# MD_02_SCHM.net
KiCad netlist of a schematic drawn in EAGLE
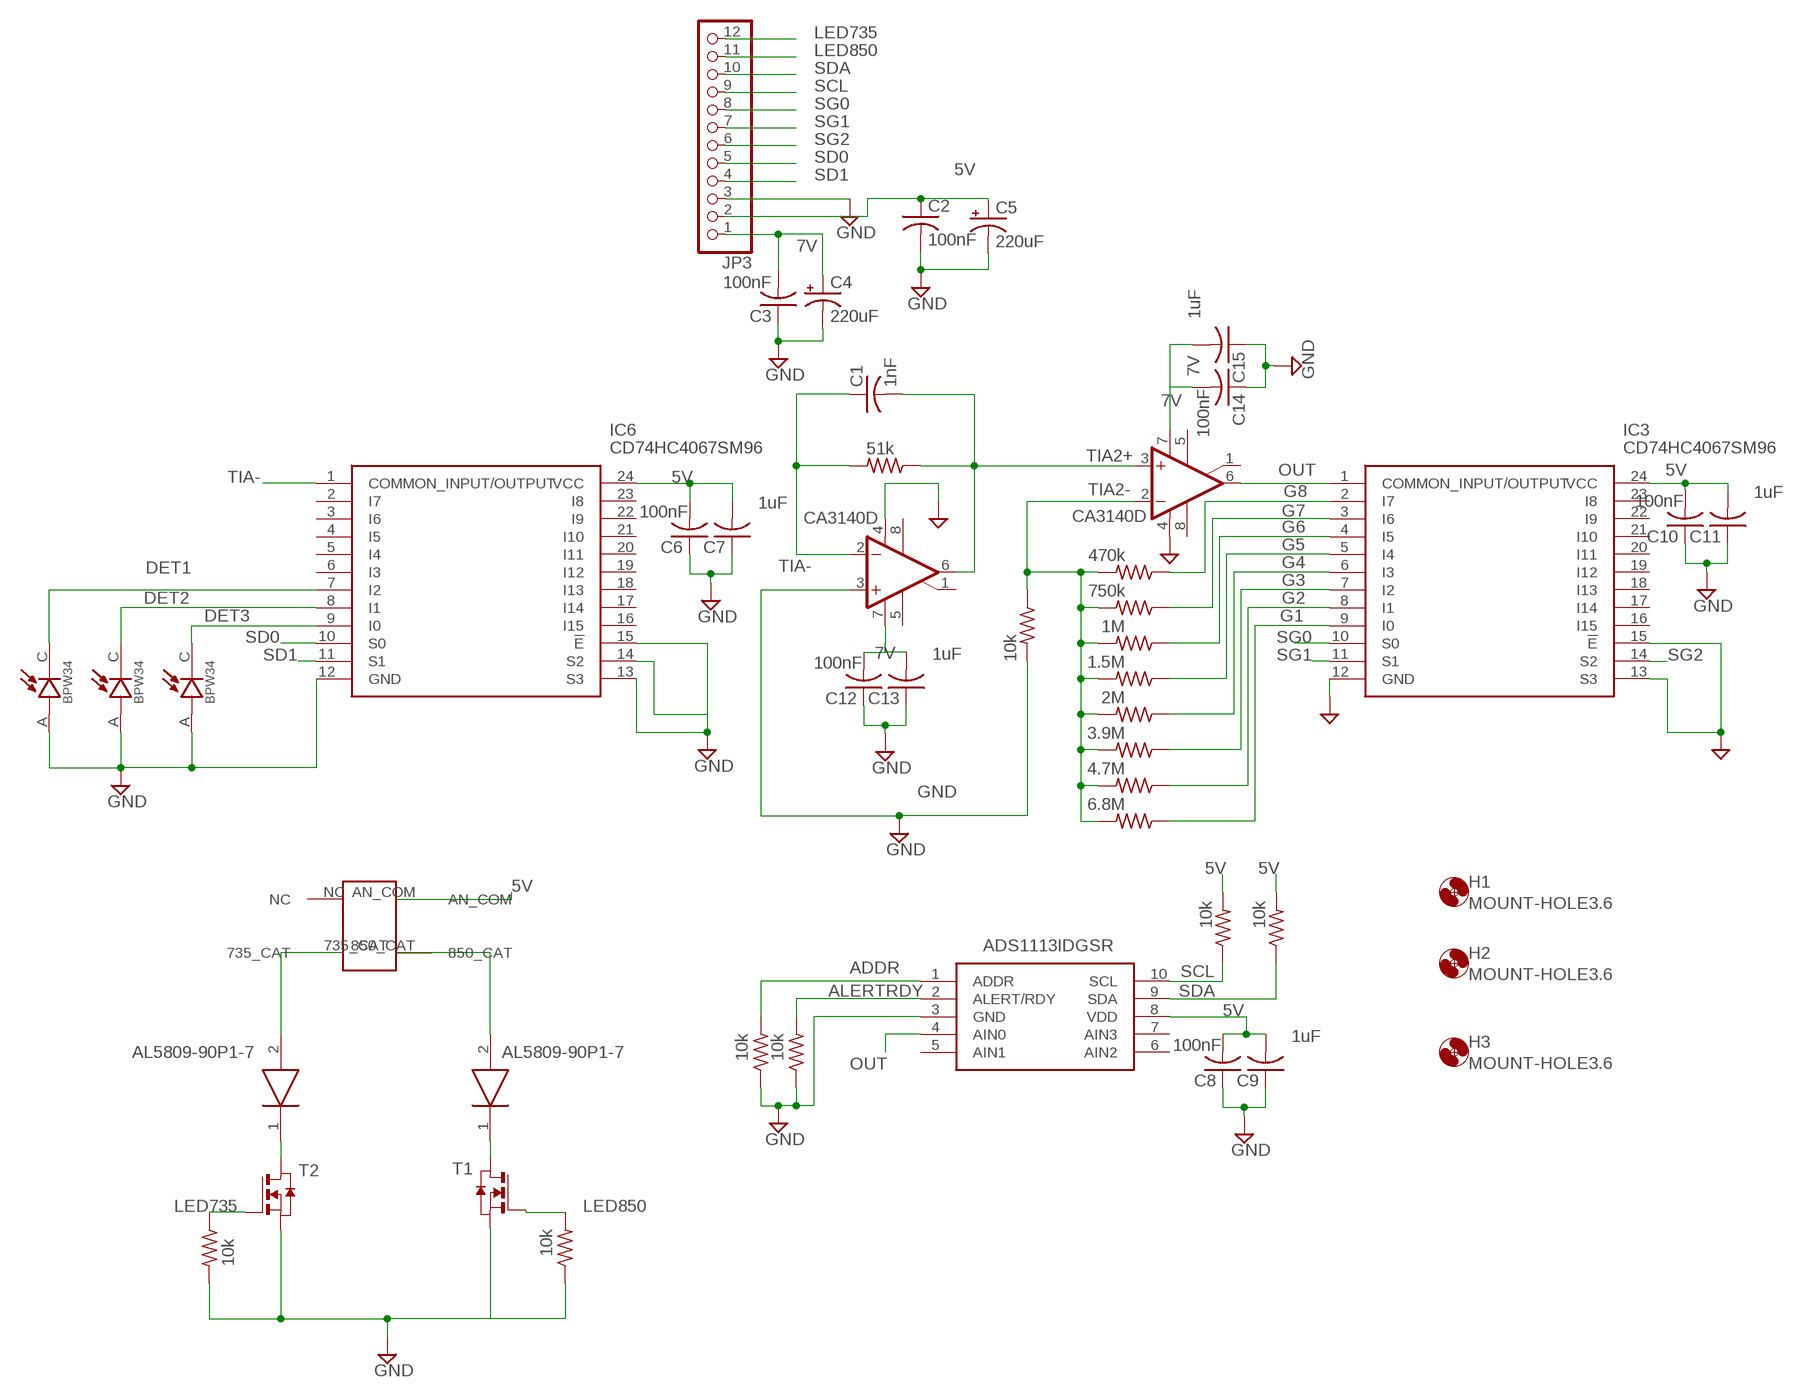
[diagram p0: schematic, sheet 1]

(export (version "E")
  (design (tool "Eeschema 10.0.6"))
  (components
    (comp (ref "C1")
      (value "1nF")
      (footprint "eagle-import:C0805")
      (libsource (lib "eagle-import") (part "C-USC0805"))
    )
    (comp (ref "C2")
      (value "100nF")
      (footprint "eagle-import:C0805")
      (libsource (lib "eagle-import") (part "C-USC0805"))
    )
    (comp (ref "C3")
      (value "100nF")
      (footprint "eagle-import:C0805")
      (libsource (lib "eagle-import") (part "C-USC0805"))
    )
    (comp (ref "C4")
      (value "220uF")
      (footprint "eagle-import:E5-6")
      (libsource (lib "eagle-import") (part "CPOL-USE5-6"))
    )
    (comp (ref "C5")
      (value "220uF")
      (footprint "eagle-import:E5-6")
      (libsource (lib "eagle-import") (part "CPOL-USE5-6"))
    )
    (comp (ref "C6")
      (value "100nF")
      (footprint "eagle-import:C0805")
      (libsource (lib "eagle-import") (part "C-USC0805"))
    )
    (comp (ref "C7")
      (value "1uF")
      (footprint "eagle-import:C0805")
      (libsource (lib "eagle-import") (part "C-USC0805"))
    )
    (comp (ref "C8")
      (value "100nF")
      (footprint "eagle-import:C0805")
      (libsource (lib "eagle-import") (part "C-USC0805"))
    )
    (comp (ref "C9")
      (value "1uF")
      (footprint "eagle-import:C0805")
      (libsource (lib "eagle-import") (part "C-USC0805"))
    )
    (comp (ref "C10")
      (value "100nF")
      (footprint "eagle-import:C0805")
      (libsource (lib "eagle-import") (part "C-USC0805"))
    )
    (comp (ref "C11")
      (value "1uF")
      (footprint "eagle-import:C0805")
      (libsource (lib "eagle-import") (part "C-USC0805"))
    )
    (comp (ref "C12")
      (value "100nF")
      (footprint "eagle-import:C0805")
      (libsource (lib "eagle-import") (part "C-USC0805"))
    )
    (comp (ref "C13")
      (value "1uF")
      (footprint "eagle-import:C0805")
      (libsource (lib "eagle-import") (part "C-USC0805"))
    )
    (comp (ref "C14")
      (value "100nF")
      (footprint "eagle-import:C0805")
      (libsource (lib "eagle-import") (part "C-USC0805"))
    )
    (comp (ref "C15")
      (value "1uF")
      (footprint "eagle-import:C0805")
      (libsource (lib "eagle-import") (part "C-USC0805"))
    )
    (comp (ref "D1")
      (value "AL5809-90P1-7")
      (footprint "eagle-import:SODFL3718X100N")
      (fields (field (name "MOUSER_PART_NUMBER") "621-AL5809-90P1-7"))
      (libsource (lib "eagle-import") (part "AL5809-90P1-7"))
    )
    (comp (ref "D2")
      (value "BPW34")
      (footprint "eagle-import:DIO_BPW34")
      (fields (field (name "MF") "Vishay Semiconductor"))
      (libsource (lib "eagle-import") (part "BPW34"))
    )
    (comp (ref "D3")
      (value "BPW34")
      (footprint "eagle-import:DIO_BPW34")
      (fields (field (name "MF") "Vishay Semiconductor"))
      (libsource (lib "eagle-import") (part "BPW34"))
    )
    (comp (ref "D4")
      (value "BPW34")
      (footprint "eagle-import:DIO_BPW34")
      (fields (field (name "MF") "Vishay Semiconductor"))
      (libsource (lib "eagle-import") (part "BPW34"))
    )
    (comp (ref "D5")
      (value "AL5809-90P1-7")
      (footprint "eagle-import:SODFL3718X100N")
      (fields (field (name "MOUSER_PART_NUMBER") "621-AL5809-90P1-7"))
      (libsource (lib "eagle-import") (part "AL5809-90P1-7"))
    )
    (comp (ref "H1")
      (value "MOUNT-HOLE3.6")
      (footprint "eagle-import:3,6")
      (libsource (lib "eagle-import") (part "MOUNT-HOLE3.6"))
    )
    (comp (ref "H2")
      (value "MOUNT-HOLE3.6")
      (footprint "eagle-import:3,6")
      (libsource (lib "eagle-import") (part "MOUNT-HOLE3.6"))
    )
    (comp (ref "H3")
      (value "MOUNT-HOLE3.6")
      (footprint "eagle-import:3,6")
      (libsource (lib "eagle-import") (part "MOUNT-HOLE3.6"))
    )
    (comp (ref "IC1")
      (value "CA3140D")
      (footprint "eagle-import:SO08")
      (libsource (lib "eagle-import") (part "CA3140D"))
    )
    (comp (ref "IC2")
      (value "CA3140D")
      (footprint "eagle-import:SO08")
      (libsource (lib "eagle-import") (part "CA3140D"))
    )
    (comp (ref "IC3")
      (value "CD74HC4067SM96")
      (footprint "eagle-import:SOP65P780X200-24N")
      (fields (field (name "MOUSER_PART_NUMBER") "595-CD74HC4067SM96"))
      (libsource (lib "eagle-import") (part "CD74HC4067SM96"))
    )
    (comp (ref "IC5")
      (value "ADS1113IDGSR")
      (footprint "eagle-import:SOP50P490X110-10N")
      (fields (field (name "MOUSER_PART_NUMBER") "595-ADS1113IDGSR"))
      (libsource (lib "eagle-import") (part "ADS1113IDGSR"))
    )
    (comp (ref "IC6")
      (value "CD74HC4067SM96")
      (footprint "eagle-import:SOP65P780X200-24N")
      (fields (field (name "MOUSER_PART_NUMBER") "595-CD74HC4067SM96"))
      (libsource (lib "eagle-import") (part "CD74HC4067SM96"))
    )
    (comp (ref "JP3")
      (value "PINHD-1X12")
      (footprint "eagle-import:1X12")
      (libsource (lib "eagle-import") (part "PINHD-1X12"))
    )
    (comp (ref "R1")
      (value "51k")
      (footprint "eagle-import:R0805")
      (libsource (lib "eagle-import") (part "R-US_R0805"))
    )
    (comp (ref "R2")
      (value "10k")
      (footprint "eagle-import:R0805")
      (libsource (lib "eagle-import") (part "R-US_R0805"))
    )
    (comp (ref "R3")
      (value "470k")
      (footprint "eagle-import:R0805")
      (libsource (lib "eagle-import") (part "R-US_R0805"))
    )
    (comp (ref "R4")
      (value "750k")
      (footprint "eagle-import:R0805")
      (libsource (lib "eagle-import") (part "R-US_R0805"))
    )
    (comp (ref "R5")
      (value "1M")
      (footprint "eagle-import:R0805")
      (libsource (lib "eagle-import") (part "R-US_R0805"))
    )
    (comp (ref "R6")
      (value "1.5M")
      (footprint "eagle-import:R0805")
      (libsource (lib "eagle-import") (part "R-US_R0805"))
    )
    (comp (ref "R7")
      (value "2M")
      (footprint "eagle-import:R0805")
      (libsource (lib "eagle-import") (part "R-US_R0805"))
    )
    (comp (ref "R8")
      (value "3.9M")
      (footprint "eagle-import:R0805")
      (libsource (lib "eagle-import") (part "R-US_R0805"))
    )
    (comp (ref "R9")
      (value "4.7M")
      (footprint "eagle-import:R0805")
      (libsource (lib "eagle-import") (part "R-US_R0805"))
    )
    (comp (ref "R10")
      (value "6.8M")
      (footprint "eagle-import:R0805")
      (libsource (lib "eagle-import") (part "R-US_R0805"))
    )
    (comp (ref "R11")
      (value "10k")
      (footprint "eagle-import:R0805")
      (libsource (lib "eagle-import") (part "R-US_R0805"))
    )
    (comp (ref "R12")
      (value "10k")
      (footprint "eagle-import:R0805")
      (libsource (lib "eagle-import") (part "R-US_R0805"))
    )
    (comp (ref "R13")
      (value "10k")
      (footprint "eagle-import:R0805")
      (libsource (lib "eagle-import") (part "R-US_R0805"))
    )
    (comp (ref "R14")
      (value "10k")
      (footprint "eagle-import:R0805")
      (libsource (lib "eagle-import") (part "R-US_R0805"))
    )
    (comp (ref "R15")
      (value "10k")
      (footprint "eagle-import:R0805")
      (libsource (lib "eagle-import") (part "R-US_R0805"))
    )
    (comp (ref "R16")
      (value "10k")
      (footprint "eagle-import:R0805")
      (libsource (lib "eagle-import") (part "R-US_R0805"))
    )
    (comp (ref "T1")
      (value "NMOSSOT23")
      (footprint "eagle-import:SOT-23")
      (libsource (lib "eagle-import") (part "NMOSSOT23"))
    )
    (comp (ref "T2")
      (value "NMOSSOT23")
      (footprint "eagle-import:SOT-23")
      (libsource (lib "eagle-import") (part "NMOSSOT23"))
    )
    (comp (ref "U$1")
      (value "SMT735D_850D")
      (footprint "eagle-import:SMT735D_850D")
      (libsource (lib "eagle-import") (part "SMT735D_850D"))
    )
  )
  (nets
    (net (code "1") (name "/5V") (class "Default")
      (node (ref "C10") (pin "2") (pinfunction "2_2") (pintype "passive"))
      (node (ref "C11") (pin "2") (pinfunction "2_2") (pintype "passive"))
      (node (ref "C2") (pin "1") (pinfunction "1_1") (pintype "passive"))
      (node (ref "C5") (pin "+") (pinfunction "+_+") (pintype "passive"))
      (node (ref "C6") (pin "2") (pinfunction "2_2") (pintype "passive"))
      (node (ref "C7") (pin "2") (pinfunction "2_2") (pintype "passive"))
      (node (ref "C8") (pin "2") (pinfunction "2_2") (pintype "passive"))
      (node (ref "C9") (pin "2") (pinfunction "2_2") (pintype "passive"))
      (node (ref "IC3") (pin "24") (pinfunction "VCC_24") (pintype "bidirectional"))
      (node (ref "IC5") (pin "8") (pinfunction "VDD_8") (pintype "bidirectional"))
      (node (ref "IC6") (pin "24") (pinfunction "VCC_24") (pintype "bidirectional"))
      (node (ref "JP3") (pin "2") (pinfunction "2_2") (pintype "passive"))
      (node (ref "R13") (pin "2") (pinfunction "2_2") (pintype "passive"))
      (node (ref "R14") (pin "2") (pinfunction "2_2") (pintype "passive"))
      (node (ref "U$1") (pin "AN_COM") (pinfunction "AN_COM_AN_COM") (pintype "bidirectional"))
    )
    (net (code "2") (name "/7V") (class "Default")
      (node (ref "C12") (pin "2") (pinfunction "2_2") (pintype "passive"))
      (node (ref "C13") (pin "2") (pinfunction "2_2") (pintype "passive"))
      (node (ref "C14") (pin "2") (pinfunction "2_2") (pintype "passive"))
      (node (ref "C15") (pin "2") (pinfunction "2_2") (pintype "passive"))
      (node (ref "C3") (pin "2") (pinfunction "2_2") (pintype "passive"))
      (node (ref "C4") (pin "+") (pinfunction "+_+") (pintype "passive"))
      (node (ref "IC1") (pin "7") (pinfunction "V+_7") (pintype "power_in"))
      (node (ref "IC2") (pin "7") (pinfunction "V+_7") (pintype "power_in"))
      (node (ref "JP3") (pin "1") (pinfunction "1_1") (pintype "passive"))
    )
    (net (code "3") (name "/ADDR") (class "Default")
      (node (ref "IC5") (pin "1") (pinfunction "ADDR_1") (pintype "bidirectional"))
      (node (ref "R11") (pin "2") (pinfunction "2_2") (pintype "passive"))
    )
    (net (code "4") (name "/ALERTRDY") (class "Default")
      (node (ref "IC5") (pin "2") (pinfunction "ALERT/RDY_2") (pintype "bidirectional"))
      (node (ref "R12") (pin "2") (pinfunction "2_2") (pintype "passive"))
    )
    (net (code "5") (name "/DET1") (class "Default")
      (node (ref "D2") (pin "C") (pinfunction "C_C") (pintype "passive"))
      (node (ref "IC6") (pin "7") (pinfunction "I2_7") (pintype "bidirectional"))
    )
    (net (code "6") (name "/DET2") (class "Default")
      (node (ref "D3") (pin "C") (pinfunction "C_C") (pintype "passive"))
      (node (ref "IC6") (pin "8") (pinfunction "I1_8") (pintype "bidirectional"))
    )
    (net (code "7") (name "/DET3") (class "Default")
      (node (ref "D4") (pin "C") (pinfunction "C_C") (pintype "passive"))
      (node (ref "IC6") (pin "9") (pinfunction "I0_9") (pintype "bidirectional"))
    )
    (net (code "8") (name "/G1") (class "Default")
      (node (ref "IC3") (pin "9") (pinfunction "I0_9") (pintype "bidirectional"))
      (node (ref "R10") (pin "1") (pinfunction "1_1") (pintype "passive"))
    )
    (net (code "9") (name "/G2") (class "Default")
      (node (ref "IC3") (pin "8") (pinfunction "I1_8") (pintype "bidirectional"))
      (node (ref "R9") (pin "1") (pinfunction "1_1") (pintype "passive"))
    )
    (net (code "10") (name "/G3") (class "Default")
      (node (ref "IC3") (pin "7") (pinfunction "I2_7") (pintype "bidirectional"))
      (node (ref "R8") (pin "1") (pinfunction "1_1") (pintype "passive"))
    )
    (net (code "11") (name "/G4") (class "Default")
      (node (ref "IC3") (pin "6") (pinfunction "I3_6") (pintype "bidirectional"))
      (node (ref "R7") (pin "1") (pinfunction "1_1") (pintype "passive"))
    )
    (net (code "12") (name "/G5") (class "Default")
      (node (ref "IC3") (pin "5") (pinfunction "I4_5") (pintype "bidirectional"))
      (node (ref "R6") (pin "1") (pinfunction "1_1") (pintype "passive"))
    )
    (net (code "13") (name "/G6") (class "Default")
      (node (ref "IC3") (pin "4") (pinfunction "I5_4") (pintype "bidirectional"))
      (node (ref "R5") (pin "1") (pinfunction "1_1") (pintype "passive"))
    )
    (net (code "14") (name "/G7") (class "Default")
      (node (ref "IC3") (pin "3") (pinfunction "I6_3") (pintype "bidirectional"))
      (node (ref "R4") (pin "1") (pinfunction "1_1") (pintype "passive"))
    )
    (net (code "15") (name "/G8") (class "Default")
      (node (ref "IC3") (pin "2") (pinfunction "I7_2") (pintype "bidirectional"))
      (node (ref "R3") (pin "1") (pinfunction "1_1") (pintype "passive"))
    )
    (net (code "16") (name "/LED735") (class "Default")
      (node (ref "JP3") (pin "12") (pinfunction "12_12") (pintype "passive"))
      (node (ref "R15") (pin "1") (pinfunction "1_1") (pintype "passive"))
      (node (ref "T2") (pin "3") (pinfunction "G_3") (pintype "passive"))
    )
    (net (code "17") (name "/LED850") (class "Default")
      (node (ref "JP3") (pin "11") (pinfunction "11_11") (pintype "passive"))
      (node (ref "R16") (pin "2") (pinfunction "2_2") (pintype "passive"))
      (node (ref "T1") (pin "3") (pinfunction "G_3") (pintype "passive"))
    )
    (net (code "18") (name "/OUT") (class "Default")
      (node (ref "IC2") (pin "6") (pinfunction "OUT_6") (pintype "output"))
      (node (ref "IC3") (pin "1") (pinfunction "COMMON_INPUT/OUTPUT_1") (pintype "bidirectional"))
      (node (ref "IC5") (pin "4") (pinfunction "AIN0_4") (pintype "bidirectional"))
    )
    (net (code "19") (name "/SCL") (class "Default")
      (node (ref "IC5") (pin "10") (pinfunction "SCL_10") (pintype "bidirectional"))
      (node (ref "JP3") (pin "9") (pinfunction "9_9") (pintype "passive"))
      (node (ref "R13") (pin "1") (pinfunction "1_1") (pintype "passive"))
    )
    (net (code "20") (name "/SD0") (class "Default")
      (node (ref "IC6") (pin "10") (pinfunction "S0_10") (pintype "bidirectional"))
      (node (ref "JP3") (pin "5") (pinfunction "5_5") (pintype "passive"))
    )
    (net (code "21") (name "/SD1") (class "Default")
      (node (ref "IC6") (pin "11") (pinfunction "S1_11") (pintype "bidirectional"))
      (node (ref "JP3") (pin "4") (pinfunction "4_4") (pintype "passive"))
    )
    (net (code "22") (name "/SDA") (class "Default")
      (node (ref "IC5") (pin "9") (pinfunction "SDA_9") (pintype "bidirectional"))
      (node (ref "JP3") (pin "10") (pinfunction "10_10") (pintype "passive"))
      (node (ref "R14") (pin "1") (pinfunction "1_1") (pintype "passive"))
    )
    (net (code "23") (name "/SG0") (class "Default")
      (node (ref "IC3") (pin "10") (pinfunction "S0_10") (pintype "bidirectional"))
      (node (ref "JP3") (pin "8") (pinfunction "8_8") (pintype "passive"))
    )
    (net (code "24") (name "/SG1") (class "Default")
      (node (ref "IC3") (pin "11") (pinfunction "S1_11") (pintype "bidirectional"))
      (node (ref "JP3") (pin "7") (pinfunction "7_7") (pintype "passive"))
    )
    (net (code "25") (name "/SG2") (class "Default")
      (node (ref "IC3") (pin "14") (pinfunction "S2_14") (pintype "bidirectional"))
      (node (ref "JP3") (pin "6") (pinfunction "6_6") (pintype "passive"))
    )
    (net (code "26") (name "/TIA-") (class "Default")
      (node (ref "C1") (pin "1") (pinfunction "1_1") (pintype "passive"))
      (node (ref "IC1") (pin "2") (pinfunction "-IN_2") (pintype "input"))
      (node (ref "IC6") (pin "1") (pinfunction "COMMON_INPUT/OUTPUT_1") (pintype "bidirectional"))
      (node (ref "R1") (pin "2") (pinfunction "2_2") (pintype "passive"))
    )
    (net (code "27") (name "/TIA2+") (class "Default")
      (node (ref "C1") (pin "2") (pinfunction "2_2") (pintype "passive"))
      (node (ref "IC1") (pin "6") (pinfunction "OUT_6") (pintype "output"))
      (node (ref "IC2") (pin "3") (pinfunction "+IN_3") (pintype "input"))
      (node (ref "R1") (pin "1") (pinfunction "1_1") (pintype "passive"))
    )
    (net (code "28") (name "/TIA2-") (class "Default")
      (node (ref "IC2") (pin "2") (pinfunction "-IN_2") (pintype "input"))
      (node (ref "R10") (pin "2") (pinfunction "2_2") (pintype "passive"))
      (node (ref "R2") (pin "1") (pinfunction "1_1") (pintype "passive"))
      (node (ref "R3") (pin "2") (pinfunction "2_2") (pintype "passive"))
      (node (ref "R4") (pin "2") (pinfunction "2_2") (pintype "passive"))
      (node (ref "R5") (pin "2") (pinfunction "2_2") (pintype "passive"))
      (node (ref "R6") (pin "2") (pinfunction "2_2") (pintype "passive"))
      (node (ref "R7") (pin "2") (pinfunction "2_2") (pintype "passive"))
      (node (ref "R8") (pin "2") (pinfunction "2_2") (pintype "passive"))
      (node (ref "R9") (pin "2") (pinfunction "2_2") (pintype "passive"))
    )
    (net (code "29") (name "GND") (class "Default")
      (node (ref "C10") (pin "1") (pinfunction "1_1") (pintype "passive"))
      (node (ref "C11") (pin "1") (pinfunction "1_1") (pintype "passive"))
      (node (ref "C12") (pin "1") (pinfunction "1_1") (pintype "passive"))
      (node (ref "C13") (pin "1") (pinfunction "1_1") (pintype "passive"))
      (node (ref "C14") (pin "1") (pinfunction "1_1") (pintype "passive"))
      (node (ref "C15") (pin "1") (pinfunction "1_1") (pintype "passive"))
      (node (ref "C2") (pin "2") (pinfunction "2_2") (pintype "passive"))
      (node (ref "C3") (pin "1") (pinfunction "1_1") (pintype "passive"))
      (node (ref "C4") (pin "-") (pinfunction "-_-") (pintype "passive"))
      (node (ref "C5") (pin "-") (pinfunction "-_-") (pintype "passive"))
      (node (ref "C6") (pin "1") (pinfunction "1_1") (pintype "passive"))
      (node (ref "C7") (pin "1") (pinfunction "1_1") (pintype "passive"))
      (node (ref "C8") (pin "1") (pinfunction "1_1") (pintype "passive"))
      (node (ref "C9") (pin "1") (pinfunction "1_1") (pintype "passive"))
      (node (ref "D2") (pin "A") (pinfunction "A_A") (pintype "passive"))
      (node (ref "D3") (pin "A") (pinfunction "A_A") (pintype "passive"))
      (node (ref "D4") (pin "A") (pinfunction "A_A") (pintype "passive"))
      (node (ref "IC1") (pin "3") (pinfunction "+IN_3") (pintype "input"))
      (node (ref "IC1") (pin "4") (pinfunction "V-_4") (pintype "power_in"))
      (node (ref "IC2") (pin "4") (pinfunction "V-_4") (pintype "power_in"))
      (node (ref "IC3") (pin "12") (pinfunction "GND_12") (pintype "bidirectional"))
      (node (ref "IC3") (pin "13") (pinfunction "S3_13") (pintype "bidirectional"))
      (node (ref "IC3") (pin "15") (pinfunction "~{E}_15") (pintype "bidirectional"))
      (node (ref "IC5") (pin "3") (pinfunction "GND_3") (pintype "bidirectional"))
      (node (ref "IC6") (pin "12") (pinfunction "GND_12") (pintype "bidirectional"))
      (node (ref "IC6") (pin "13") (pinfunction "S3_13") (pintype "bidirectional"))
      (node (ref "IC6") (pin "14") (pinfunction "S2_14") (pintype "bidirectional"))
      (node (ref "IC6") (pin "15") (pinfunction "~{E}_15") (pintype "bidirectional"))
      (node (ref "JP3") (pin "3") (pinfunction "3_3") (pintype "passive"))
      (node (ref "R11") (pin "1") (pinfunction "1_1") (pintype "passive"))
      (node (ref "R12") (pin "1") (pinfunction "1_1") (pintype "passive"))
      (node (ref "R15") (pin "2") (pinfunction "2_2") (pintype "passive"))
      (node (ref "R16") (pin "1") (pinfunction "1_1") (pintype "passive"))
      (node (ref "R2") (pin "2") (pinfunction "2_2") (pintype "passive"))
      (node (ref "T1") (pin "2") (pinfunction "S_2") (pintype "passive"))
      (node (ref "T2") (pin "2") (pinfunction "S_2") (pintype "passive"))
    )
    (net (code "30") (name "Net-(D1-A)") (class "Default")
      (node (ref "D1") (pin "2") (pinfunction "A_2") (pintype "bidirectional"))
      (node (ref "U$1") (pin "850_CAT") (pinfunction "850_CAT_850_CAT") (pintype "bidirectional"))
    )
    (net (code "31") (name "Net-(D1-K)") (class "Default")
      (node (ref "D1") (pin "1") (pinfunction "K_1") (pintype "bidirectional"))
      (node (ref "T1") (pin "1") (pinfunction "D_1") (pintype "passive"))
    )
    (net (code "32") (name "Net-(D5-A)") (class "Default")
      (node (ref "D5") (pin "2") (pinfunction "A_2") (pintype "bidirectional"))
      (node (ref "U$1") (pin "735_CAT") (pinfunction "735_CAT_735_CAT") (pintype "bidirectional"))
    )
    (net (code "33") (name "Net-(D5-K)") (class "Default")
      (node (ref "D5") (pin "1") (pinfunction "K_1") (pintype "bidirectional"))
      (node (ref "T2") (pin "1") (pinfunction "D_1") (pintype "passive"))
    )
    (net (code "34") (name "unconnected-(IC1-CMP-Pad8)") (class "Default")
      (node (ref "IC1") (pin "8") (pinfunction "CMP_8") (pintype "passive"))
    )
    (net (code "35") (name "unconnected-(IC1-ON-Pad5)") (class "Default")
      (node (ref "IC1") (pin "5") (pinfunction "ON_5") (pintype "passive"))
    )
    (net (code "36") (name "unconnected-(IC1-ON{slash}CMP-Pad1)") (class "Default")
      (node (ref "IC1") (pin "1") (pinfunction "ON/CMP_1") (pintype "passive"))
    )
    (net (code "37") (name "unconnected-(IC2-CMP-Pad8)") (class "Default")
      (node (ref "IC2") (pin "8") (pinfunction "CMP_8") (pintype "passive"))
    )
    (net (code "38") (name "unconnected-(IC2-ON-Pad5)") (class "Default")
      (node (ref "IC2") (pin "5") (pinfunction "ON_5") (pintype "passive"))
    )
    (net (code "39") (name "unconnected-(IC2-ON{slash}CMP-Pad1)") (class "Default")
      (node (ref "IC2") (pin "1") (pinfunction "ON/CMP_1") (pintype "passive"))
    )
    (net (code "40") (name "unconnected-(IC3-I8-Pad23)") (class "Default")
      (node (ref "IC3") (pin "23") (pinfunction "I8_23") (pintype "bidirectional"))
    )
    (net (code "41") (name "unconnected-(IC3-I9-Pad22)") (class "Default")
      (node (ref "IC3") (pin "22") (pinfunction "I9_22") (pintype "bidirectional"))
    )
    (net (code "42") (name "unconnected-(IC3-I10-Pad21)") (class "Default")
      (node (ref "IC3") (pin "21") (pinfunction "I10_21") (pintype "bidirectional"))
    )
    (net (code "43") (name "unconnected-(IC3-I11-Pad20)") (class "Default")
      (node (ref "IC3") (pin "20") (pinfunction "I11_20") (pintype "bidirectional"))
    )
    (net (code "44") (name "unconnected-(IC3-I12-Pad19)") (class "Default")
      (node (ref "IC3") (pin "19") (pinfunction "I12_19") (pintype "bidirectional"))
    )
    (net (code "45") (name "unconnected-(IC3-I13-Pad18)") (class "Default")
      (node (ref "IC3") (pin "18") (pinfunction "I13_18") (pintype "bidirectional"))
    )
    (net (code "46") (name "unconnected-(IC3-I14-Pad17)") (class "Default")
      (node (ref "IC3") (pin "17") (pinfunction "I14_17") (pintype "bidirectional"))
    )
    (net (code "47") (name "unconnected-(IC3-I15-Pad16)") (class "Default")
      (node (ref "IC3") (pin "16") (pinfunction "I15_16") (pintype "bidirectional"))
    )
    (net (code "48") (name "unconnected-(IC5-AIN1-Pad5)") (class "Default")
      (node (ref "IC5") (pin "5") (pinfunction "AIN1_5") (pintype "bidirectional"))
    )
    (net (code "49") (name "unconnected-(IC5-AIN2-Pad6)") (class "Default")
      (node (ref "IC5") (pin "6") (pinfunction "AIN2_6") (pintype "bidirectional"))
    )
    (net (code "50") (name "unconnected-(IC5-AIN3-Pad7)") (class "Default")
      (node (ref "IC5") (pin "7") (pinfunction "AIN3_7") (pintype "bidirectional"))
    )
    (net (code "51") (name "unconnected-(IC6-I3-Pad6)") (class "Default")
      (node (ref "IC6") (pin "6") (pinfunction "I3_6") (pintype "bidirectional"))
    )
    (net (code "52") (name "unconnected-(IC6-I4-Pad5)") (class "Default")
      (node (ref "IC6") (pin "5") (pinfunction "I4_5") (pintype "bidirectional"))
    )
    (net (code "53") (name "unconnected-(IC6-I5-Pad4)") (class "Default")
      (node (ref "IC6") (pin "4") (pinfunction "I5_4") (pintype "bidirectional"))
    )
    (net (code "54") (name "unconnected-(IC6-I6-Pad3)") (class "Default")
      (node (ref "IC6") (pin "3") (pinfunction "I6_3") (pintype "bidirectional"))
    )
    (net (code "55") (name "unconnected-(IC6-I7-Pad2)") (class "Default")
      (node (ref "IC6") (pin "2") (pinfunction "I7_2") (pintype "bidirectional"))
    )
    (net (code "56") (name "unconnected-(IC6-I8-Pad23)") (class "Default")
      (node (ref "IC6") (pin "23") (pinfunction "I8_23") (pintype "bidirectional"))
    )
    (net (code "57") (name "unconnected-(IC6-I9-Pad22)") (class "Default")
      (node (ref "IC6") (pin "22") (pinfunction "I9_22") (pintype "bidirectional"))
    )
    (net (code "58") (name "unconnected-(IC6-I10-Pad21)") (class "Default")
      (node (ref "IC6") (pin "21") (pinfunction "I10_21") (pintype "bidirectional"))
    )
    (net (code "59") (name "unconnected-(IC6-I11-Pad20)") (class "Default")
      (node (ref "IC6") (pin "20") (pinfunction "I11_20") (pintype "bidirectional"))
    )
    (net (code "60") (name "unconnected-(IC6-I12-Pad19)") (class "Default")
      (node (ref "IC6") (pin "19") (pinfunction "I12_19") (pintype "bidirectional"))
    )
    (net (code "61") (name "unconnected-(IC6-I13-Pad18)") (class "Default")
      (node (ref "IC6") (pin "18") (pinfunction "I13_18") (pintype "bidirectional"))
    )
    (net (code "62") (name "unconnected-(IC6-I14-Pad17)") (class "Default")
      (node (ref "IC6") (pin "17") (pinfunction "I14_17") (pintype "bidirectional"))
    )
    (net (code "63") (name "unconnected-(IC6-I15-Pad16)") (class "Default")
      (node (ref "IC6") (pin "16") (pinfunction "I15_16") (pintype "bidirectional"))
    )
    (net (code "64") (name "unconnected-(U$1-PadNC)") (class "Default")
      (node (ref "U$1") (pin "NC") (pinfunction "NC_NC") (pintype "bidirectional"))
    )
  )
)
